# touch.net
KiCad netlist of a schematic drawn in EAGLE
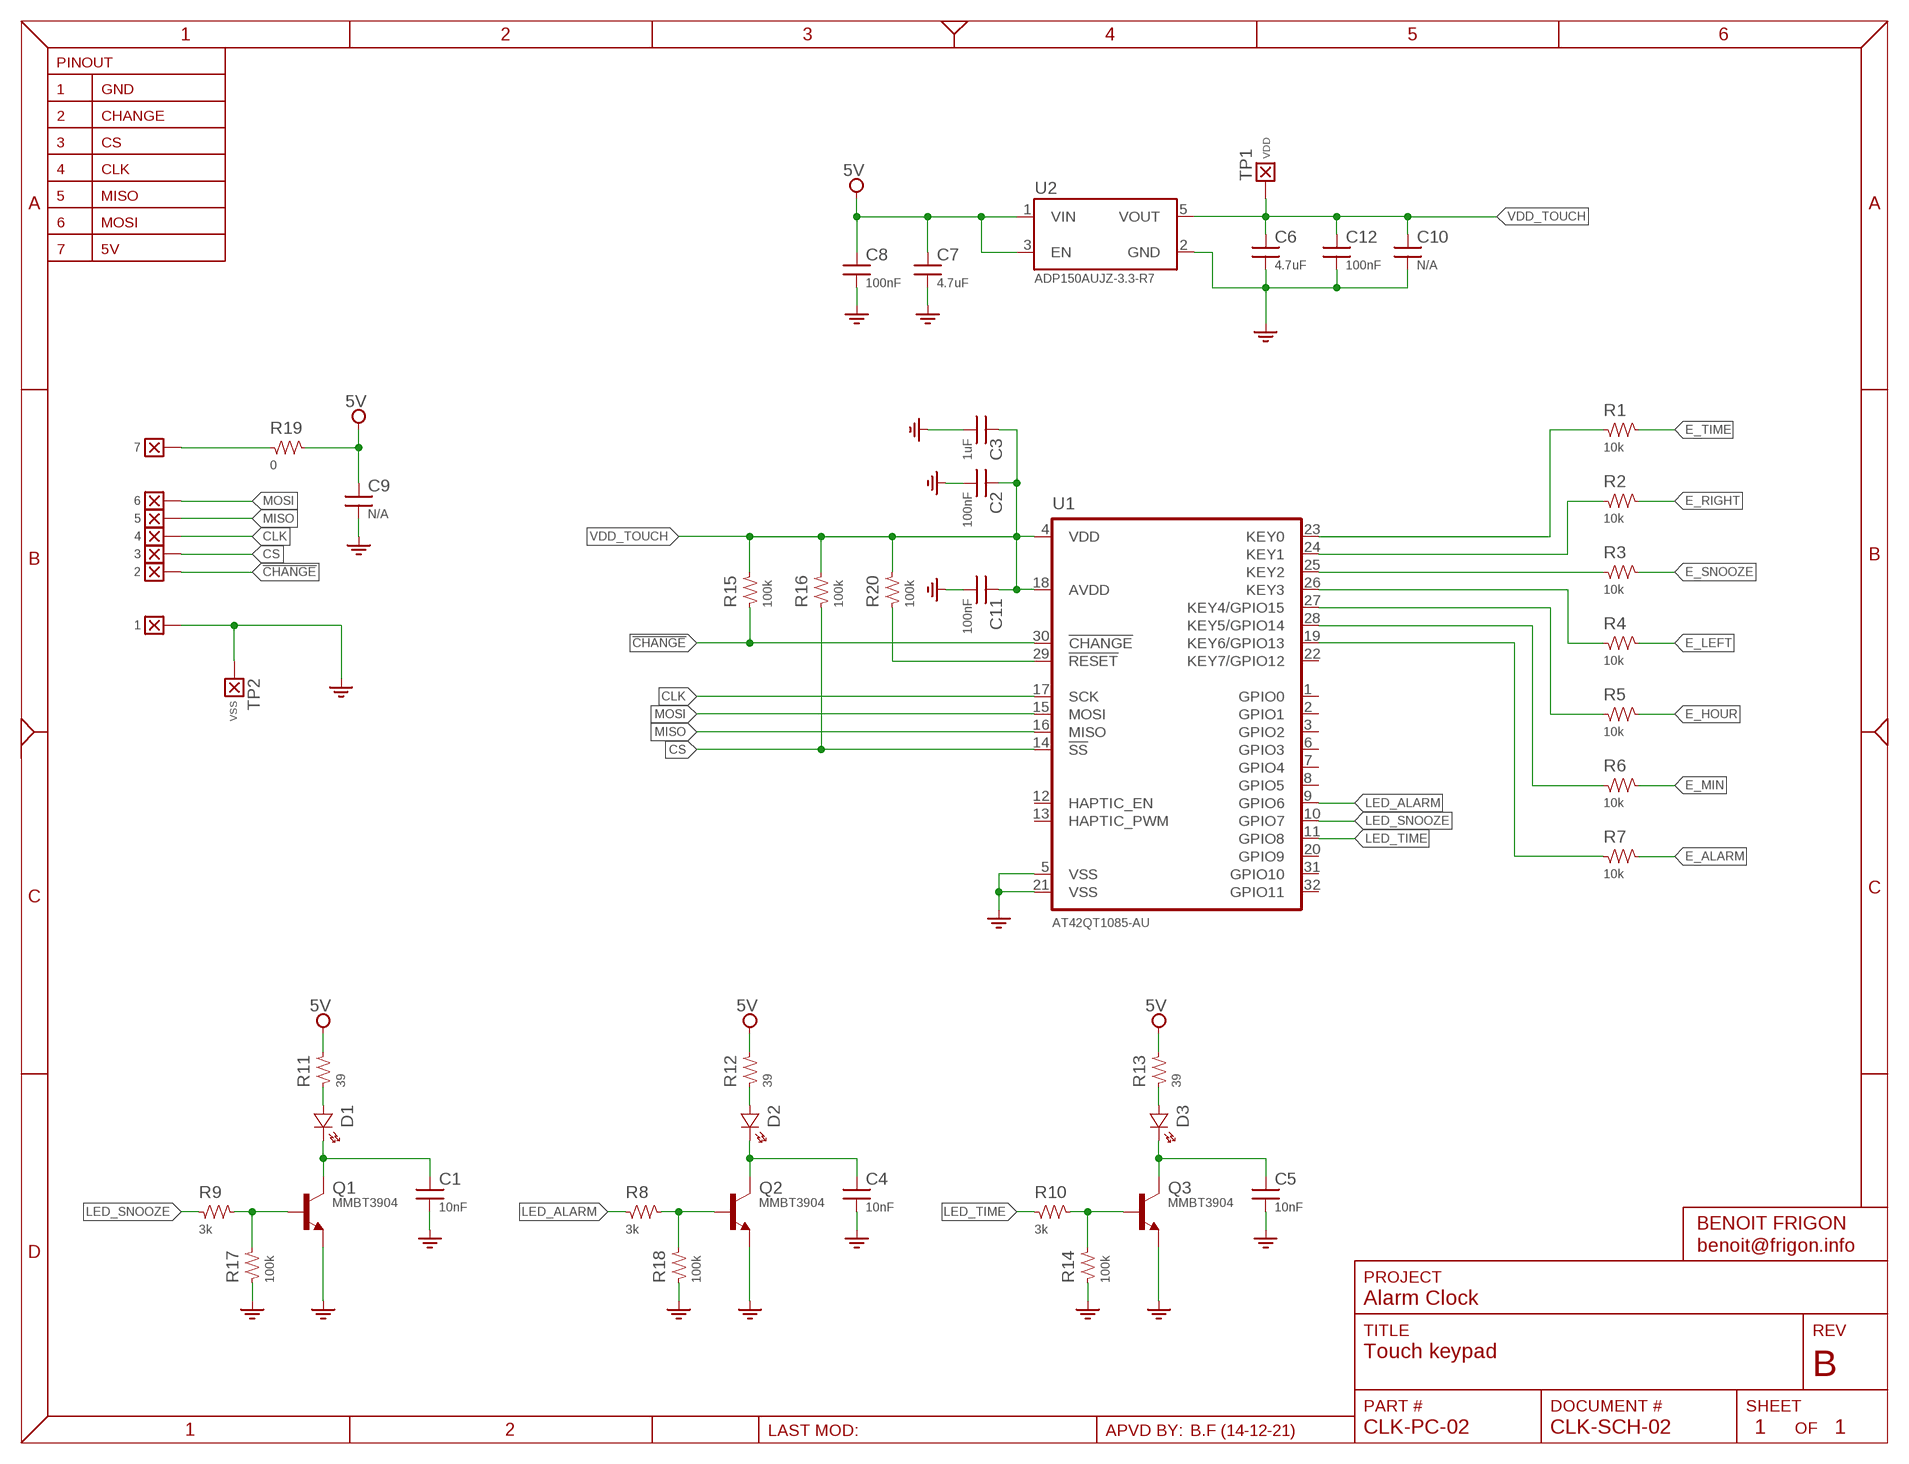
[diagram p0: schematic, sheet 1]

(export (version "E")
  (design (tool "Eeschema 10.0.6"))
  (components
    (comp (ref "!CHANGE")
      (value "2")
      (footprint "eagle-import:WIRE_SMT_125X50")
      (fields (field (name "BOM") "FALSE"))
      (libsource (lib "eagle-import") (part "WIRE-?125X50"))
    )
    (comp (ref "5V")
      (value "7")
      (footprint "eagle-import:WIRE_SMT_150X75")
      (libsource (lib "eagle-import") (part "WIRE-?150X75"))
    )
    (comp (ref "C1")
      (value "10nF")
      (footprint "eagle-import:SMD_0603")
      (libsource (lib "eagle-import") (part "CAP-0603"))
    )
    (comp (ref "C2")
      (value "100nF")
      (footprint "eagle-import:SMD_0603")
      (libsource (lib "eagle-import") (part "CAP-0603"))
    )
    (comp (ref "C3")
      (value "1uF")
      (footprint "eagle-import:SMD_1206")
      (description "{DESCRIPTION} - SMT 1206 - {value}")
      (fields (field (name "PACKAGE") "SMT 1206"))
      (libsource (lib "eagle-import") (part "CAP-1206"))
    )
    (comp (ref "C4")
      (value "10nF")
      (footprint "eagle-import:SMD_0603")
      (libsource (lib "eagle-import") (part "CAP-0603"))
    )
    (comp (ref "C5")
      (value "10nF")
      (footprint "eagle-import:SMD_0603")
      (libsource (lib "eagle-import") (part "CAP-0603"))
    )
    (comp (ref "C6")
      (value "4.7uF")
      (footprint "eagle-import:SMD_1206")
      (description "{DESCRIPTION} - SMT 1206 - {value}")
      (fields (field (name "PACKAGE") "SMT 1206"))
      (libsource (lib "eagle-import") (part "CAP-1206"))
    )
    (comp (ref "C7")
      (value "4.7uF")
      (footprint "eagle-import:SMD_1206")
      (description "{DESCRIPTION} - SMT 1206 - {value}")
      (fields (field (name "PACKAGE") "SMT 1206"))
      (libsource (lib "eagle-import") (part "CAP-1206"))
    )
    (comp (ref "C8")
      (value "100nF")
      (footprint "eagle-import:SMD_0603")
      (description "{DESCRIPTION} - SMT 0603 - {value}")
      (fields (field (name "PACKAGE") "SMT 0603"))
      (libsource (lib "eagle-import") (part "CAP-0603"))
    )
    (comp (ref "C9")
      (value "N/A")
      (footprint "eagle-import:SMD_1206")
      (libsource (lib "eagle-import") (part "CAP-1206"))
    )
    (comp (ref "C10")
      (value "N/A")
      (footprint "eagle-import:SMD_1206")
      (libsource (lib "eagle-import") (part "CAP-1206"))
    )
    (comp (ref "C11")
      (value "100nF")
      (footprint "eagle-import:SMD_0603")
      (description "{DESCRIPTION} - SMT 0603 - {value}")
      (fields (field (name "PACKAGE") "SMT 0603"))
      (libsource (lib "eagle-import") (part "CAP-0603"))
    )
    (comp (ref "C12")
      (value "100nF")
      (footprint "eagle-import:SMD_0603")
      (libsource (lib "eagle-import") (part "CAP-0603"))
    )
    (comp (ref "CLK")
      (value "4")
      (footprint "eagle-import:WIRE_SMT_125X50")
      (libsource (lib "eagle-import") (part "WIRE-?125X50"))
    )
    (comp (ref "CS")
      (value "3")
      (footprint "eagle-import:WIRE_SMT_125X50")
      (libsource (lib "eagle-import") (part "WIRE-?125X50"))
    )
    (comp (ref "D1")
      (value "{ATTR:COLOR}")
      (footprint "eagle-import:P47F")
      (description "{DESCRIPTION} - Red")
      (fields (field (name "MFG") "OSRAM") (field (name "COLOR") "Red"))
      (libsource (lib "eagle-import") (part "-P47FLR"))
    )
    (comp (ref "D2")
      (value "{ATTR:COLOR}")
      (footprint "eagle-import:P47F")
      (description "{DESCRIPTION} - Red")
      (fields (field (name "MFG") "OSRAM") (field (name "COLOR") "Red"))
      (libsource (lib "eagle-import") (part "-P47FLR"))
    )
    (comp (ref "D3")
      (value "{ATTR:COLOR}")
      (footprint "eagle-import:P47F")
      (description "{DESCRIPTION} - Red")
      (fields (field (name "MFG") "OSRAM") (field (name "COLOR") "Red"))
      (libsource (lib "eagle-import") (part "-P47FLR"))
    )
    (comp (ref "GND")
      (value "1")
      (footprint "eagle-import:WIRE_SMT_150X75")
      (libsource (lib "eagle-import") (part "WIRE-?150X75"))
    )
    (comp (ref "MISO")
      (value "5")
      (footprint "eagle-import:WIRE_SMT_125X50")
      (libsource (lib "eagle-import") (part "WIRE-?125X50"))
    )
    (comp (ref "MOSI")
      (value "6")
      (footprint "eagle-import:WIRE_SMT_125X50")
      (libsource (lib "eagle-import") (part "WIRE-?125X50"))
    )
    (comp (ref "Q1")
      (value "MMBT3904")
      (footprint "eagle-import:SOT23")
      (libsource (lib "eagle-import") (part "MMBT3904"))
    )
    (comp (ref "Q2")
      (value "MMBT3904")
      (footprint "eagle-import:SOT23")
      (libsource (lib "eagle-import") (part "MMBT3904"))
    )
    (comp (ref "Q3")
      (value "MMBT3904")
      (footprint "eagle-import:SOT23")
      (libsource (lib "eagle-import") (part "MMBT3904"))
    )
    (comp (ref "R1")
      (value "10k")
      (footprint "eagle-import:SMD_0603")
      (libsource (lib "eagle-import") (part "RES-0603"))
    )
    (comp (ref "R2")
      (value "10k")
      (footprint "eagle-import:SMD_0603")
      (description "{DESCRIPTION} - SMT 0603 - {VALUE}")
      (fields (field (name "PACKAGE") "SMT 0603"))
      (libsource (lib "eagle-import") (part "RES-0603"))
    )
    (comp (ref "R3")
      (value "10k")
      (footprint "eagle-import:SMD_0603")
      (description "{DESCRIPTION} - SMT 0603 - {VALUE}")
      (fields (field (name "PACKAGE") "SMT 0603"))
      (libsource (lib "eagle-import") (part "RES-0603"))
    )
    (comp (ref "R4")
      (value "10k")
      (footprint "eagle-import:SMD_0603")
      (description "{DESCRIPTION} - SMT 0603 - {VALUE}")
      (fields (field (name "PACKAGE") "SMT 0603"))
      (libsource (lib "eagle-import") (part "RES-0603"))
    )
    (comp (ref "R5")
      (value "10k")
      (footprint "eagle-import:SMD_0603")
      (description "{DESCRIPTION} - SMT 0603 - {VALUE}")
      (fields (field (name "PACKAGE") "SMT 0603"))
      (libsource (lib "eagle-import") (part "RES-0603"))
    )
    (comp (ref "R6")
      (value "10k")
      (footprint "eagle-import:SMD_0603")
      (description "{DESCRIPTION} - SMT 0603 - {VALUE}")
      (fields (field (name "PACKAGE") "SMT 0603"))
      (libsource (lib "eagle-import") (part "RES-0603"))
    )
    (comp (ref "R7")
      (value "10k")
      (footprint "eagle-import:SMD_0603")
      (description "{DESCRIPTION} - SMT 0603 - {VALUE}")
      (fields (field (name "PACKAGE") "SMT 0603"))
      (libsource (lib "eagle-import") (part "RES-0603"))
    )
    (comp (ref "R8")
      (value "3k")
      (footprint "eagle-import:SMD_0603")
      (libsource (lib "eagle-import") (part "RES-0603"))
    )
    (comp (ref "R9")
      (value "3k")
      (footprint "eagle-import:SMD_0603")
      (libsource (lib "eagle-import") (part "RES-0603"))
    )
    (comp (ref "R10")
      (value "3k")
      (footprint "eagle-import:SMD_0603")
      (libsource (lib "eagle-import") (part "RES-0603"))
    )
    (comp (ref "R11")
      (value "39")
      (footprint "eagle-import:SMD_0603")
      (libsource (lib "eagle-import") (part "RES-0603"))
    )
    (comp (ref "R12")
      (value "39")
      (footprint "eagle-import:SMD_0603")
      (libsource (lib "eagle-import") (part "RES-0603"))
    )
    (comp (ref "R13")
      (value "39")
      (footprint "eagle-import:SMD_0603")
      (libsource (lib "eagle-import") (part "RES-0603"))
    )
    (comp (ref "R14")
      (value "100k")
      (footprint "eagle-import:SMD_0603")
      (libsource (lib "eagle-import") (part "RES-0603"))
    )
    (comp (ref "R15")
      (value "100k")
      (footprint "eagle-import:SMD_0603")
      (libsource (lib "eagle-import") (part "RES-0603"))
    )
    (comp (ref "R16")
      (value "100k")
      (footprint "eagle-import:SMD_0603")
      (libsource (lib "eagle-import") (part "RES-0603"))
    )
    (comp (ref "R17")
      (value "100k")
      (footprint "eagle-import:SMD_0603")
      (libsource (lib "eagle-import") (part "RES-0603"))
    )
    (comp (ref "R18")
      (value "100k")
      (footprint "eagle-import:SMD_0603")
      (libsource (lib "eagle-import") (part "RES-0603"))
    )
    (comp (ref "R19")
      (value "0")
      (footprint "eagle-import:SMD_1206")
      (libsource (lib "eagle-import") (part "RES-1206"))
    )
    (comp (ref "R20")
      (value "100k")
      (footprint "eagle-import:SMD_0603")
      (description "{DESCRIPTION} - SMT 0603 - {VALUE}")
      (fields (field (name "PACKAGE") "SMT 0603"))
      (libsource (lib "eagle-import") (part "RES-0603"))
    )
    (comp (ref "TP1")
      (value "VDD")
      (footprint "eagle-import:TP_050")
      (libsource (lib "eagle-import") (part "TEST_POINT-050"))
    )
    (comp (ref "TP2")
      (value "VSS")
      (footprint "eagle-import:TP_050")
      (libsource (lib "eagle-import") (part "TEST_POINT-050"))
    )
    (comp (ref "U1")
      (value "AT42QT1085-AU")
      (footprint "eagle-import:TQFP-7X7-32")
      (libsource (lib "eagle-import") (part "AT42QT1085-?AU"))
    )
    (comp (ref "U2")
      (value "ADP150AUJZ-3.3-R7")
      (footprint "eagle-import:SOT23-5")
      (description "{DESCRIPTION} - 3.3v")
      (fields (field (name "MFG") "Analog Devices"))
      (libsource (lib "eagle-import") (part "ADP150A?Z--R7UJ3.3"))
    )
  )
  (nets
    (net (code "1") (name "/~{CHANGE}") (class "Default")
      (node (ref "!CHANGE") (pin "1") (pinfunction "P$1_1") (pintype "bidirectional"))
      (node (ref "R15") (pin "1") (pinfunction "1_1") (pintype "passive"))
      (node (ref "U1") (pin "30") (pinfunction "~{CHANGE}_30") (pintype "open_collector"))
    )
    (net (code "2") (name "5V") (class "Default")
      (node (ref "C7") (pin "1") (pinfunction "1_1") (pintype "passive"))
      (node (ref "C8") (pin "1") (pinfunction "1_1") (pintype "passive"))
      (node (ref "C9") (pin "1") (pinfunction "1_1") (pintype "passive"))
      (node (ref "R11") (pin "2") (pinfunction "2_2") (pintype "passive"))
      (node (ref "R12") (pin "2") (pinfunction "2_2") (pintype "passive"))
      (node (ref "R13") (pin "2") (pinfunction "2_2") (pintype "passive"))
      (node (ref "R19") (pin "2") (pinfunction "2_2") (pintype "passive"))
      (node (ref "U2") (pin "1") (pinfunction "VIN_1") (pintype "power_in"))
      (node (ref "U2") (pin "3") (pinfunction "EN_3") (pintype "input"))
    )
    (net (code "3") (name "CLK") (class "Default")
      (node (ref "CLK") (pin "1") (pinfunction "P$1_1") (pintype "bidirectional"))
      (node (ref "U1") (pin "17") (pinfunction "SCK_17") (pintype "input"))
    )
    (net (code "4") (name "CS") (class "Default")
      (node (ref "CS") (pin "1") (pinfunction "P$1_1") (pintype "bidirectional"))
      (node (ref "R16") (pin "1") (pinfunction "1_1") (pintype "passive"))
      (node (ref "U1") (pin "14") (pinfunction "~{SS}_14") (pintype "input"))
    )
    (net (code "5") (name "E_ALARM") (class "Default")
      (node (ref "R7") (pin "2") (pinfunction "2_2") (pintype "passive"))
    )
    (net (code "6") (name "E_HOUR") (class "Default")
      (node (ref "R5") (pin "2") (pinfunction "2_2") (pintype "passive"))
    )
    (net (code "7") (name "E_LEFT") (class "Default")
      (node (ref "R4") (pin "2") (pinfunction "2_2") (pintype "passive"))
    )
    (net (code "8") (name "E_MIN") (class "Default")
      (node (ref "R6") (pin "2") (pinfunction "2_2") (pintype "passive"))
    )
    (net (code "9") (name "E_RIGHT") (class "Default")
      (node (ref "R2") (pin "2") (pinfunction "2_2") (pintype "passive"))
    )
    (net (code "10") (name "E_SNOOZE") (class "Default")
      (node (ref "R3") (pin "2") (pinfunction "2_2") (pintype "passive"))
    )
    (net (code "11") (name "E_TIME") (class "Default")
      (node (ref "R1") (pin "2") (pinfunction "2_2") (pintype "passive"))
    )
    (net (code "12") (name "GND") (class "Default")
      (node (ref "C1") (pin "2") (pinfunction "2_2") (pintype "passive"))
      (node (ref "C10") (pin "2") (pinfunction "2_2") (pintype "passive"))
      (node (ref "C11") (pin "2") (pinfunction "2_2") (pintype "passive"))
      (node (ref "C12") (pin "2") (pinfunction "2_2") (pintype "passive"))
      (node (ref "C2") (pin "2") (pinfunction "2_2") (pintype "passive"))
      (node (ref "C3") (pin "2") (pinfunction "2_2") (pintype "passive"))
      (node (ref "C4") (pin "2") (pinfunction "2_2") (pintype "passive"))
      (node (ref "C5") (pin "2") (pinfunction "2_2") (pintype "passive"))
      (node (ref "C6") (pin "2") (pinfunction "2_2") (pintype "passive"))
      (node (ref "C7") (pin "2") (pinfunction "2_2") (pintype "passive"))
      (node (ref "C8") (pin "2") (pinfunction "2_2") (pintype "passive"))
      (node (ref "C9") (pin "2") (pinfunction "2_2") (pintype "passive"))
      (node (ref "GND") (pin "1") (pinfunction "P$1_1") (pintype "bidirectional"))
      (node (ref "Q1") (pin "2") (pinfunction "E_2") (pintype "passive"))
      (node (ref "Q2") (pin "2") (pinfunction "E_2") (pintype "passive"))
      (node (ref "Q3") (pin "2") (pinfunction "E_2") (pintype "passive"))
      (node (ref "R14") (pin "1") (pinfunction "1_1") (pintype "passive"))
      (node (ref "R17") (pin "1") (pinfunction "1_1") (pintype "passive"))
      (node (ref "R18") (pin "1") (pinfunction "1_1") (pintype "passive"))
      (node (ref "TP2") (pin "1") (pinfunction "P$1_1") (pintype "bidirectional"))
      (node (ref "U1") (pin "21") (pinfunction "VSS_21") (pintype "power_in"))
      (node (ref "U1") (pin "5") (pinfunction "VSS_5") (pintype "power_in"))
      (node (ref "U2") (pin "2") (pinfunction "GND_2") (pintype "power_in"))
    )
    (net (code "13") (name "LED_ALARM") (class "Default")
      (node (ref "R8") (pin "1") (pinfunction "1_1") (pintype "passive"))
      (node (ref "U1") (pin "9") (pinfunction "GPIO6_9") (pintype "bidirectional"))
    )
    (net (code "14") (name "LED_SNOOZE") (class "Default")
      (node (ref "R9") (pin "1") (pinfunction "1_1") (pintype "passive"))
      (node (ref "U1") (pin "10") (pinfunction "GPIO7_10") (pintype "bidirectional"))
    )
    (net (code "15") (name "LED_TIME") (class "Default")
      (node (ref "R10") (pin "1") (pinfunction "1_1") (pintype "passive"))
      (node (ref "U1") (pin "11") (pinfunction "GPIO8_11") (pintype "bidirectional"))
    )
    (net (code "16") (name "MISO") (class "Default")
      (node (ref "MISO") (pin "1") (pinfunction "P$1_1") (pintype "bidirectional"))
      (node (ref "U1") (pin "16") (pinfunction "MISO_16") (pintype "output"))
    )
    (net (code "17") (name "MOSI") (class "Default")
      (node (ref "MOSI") (pin "1") (pinfunction "P$1_1") (pintype "bidirectional"))
      (node (ref "U1") (pin "15") (pinfunction "MOSI_15") (pintype "input"))
    )
    (net (code "18") (name "Net-(5V-P$1)") (class "Default")
      (node (ref "5V") (pin "1") (pinfunction "P$1_1") (pintype "bidirectional"))
      (node (ref "R19") (pin "1") (pinfunction "1_1") (pintype "passive"))
    )
    (net (code "19") (name "Net-(D1-PadA)") (class "Default")
      (node (ref "D1") (pin "A") (pinfunction "A_A") (pintype "passive"))
      (node (ref "R11") (pin "1") (pinfunction "1_1") (pintype "passive"))
    )
    (net (code "20") (name "Net-(D2-PadA)") (class "Default")
      (node (ref "D2") (pin "A") (pinfunction "A_A") (pintype "passive"))
      (node (ref "R12") (pin "1") (pinfunction "1_1") (pintype "passive"))
    )
    (net (code "21") (name "Net-(D3-PadA)") (class "Default")
      (node (ref "D3") (pin "A") (pinfunction "A_A") (pintype "passive"))
      (node (ref "R13") (pin "1") (pinfunction "1_1") (pintype "passive"))
    )
    (net (code "22") (name "Net-(Q1-B)") (class "Default")
      (node (ref "Q1") (pin "1") (pinfunction "B_1") (pintype "passive"))
      (node (ref "R17") (pin "2") (pinfunction "2_2") (pintype "passive"))
      (node (ref "R9") (pin "2") (pinfunction "2_2") (pintype "passive"))
    )
    (net (code "23") (name "Net-(Q1-C)") (class "Default")
      (node (ref "C1") (pin "1") (pinfunction "1_1") (pintype "passive"))
      (node (ref "D1") (pin "K") (pinfunction "K_K") (pintype "passive"))
      (node (ref "Q1") (pin "3") (pinfunction "C_3") (pintype "passive"))
    )
    (net (code "24") (name "Net-(Q2-B)") (class "Default")
      (node (ref "Q2") (pin "1") (pinfunction "B_1") (pintype "passive"))
      (node (ref "R18") (pin "2") (pinfunction "2_2") (pintype "passive"))
      (node (ref "R8") (pin "2") (pinfunction "2_2") (pintype "passive"))
    )
    (net (code "25") (name "Net-(Q2-C)") (class "Default")
      (node (ref "C4") (pin "1") (pinfunction "1_1") (pintype "passive"))
      (node (ref "D2") (pin "K") (pinfunction "K_K") (pintype "passive"))
      (node (ref "Q2") (pin "3") (pinfunction "C_3") (pintype "passive"))
    )
    (net (code "26") (name "Net-(Q3-B)") (class "Default")
      (node (ref "Q3") (pin "1") (pinfunction "B_1") (pintype "passive"))
      (node (ref "R10") (pin "2") (pinfunction "2_2") (pintype "passive"))
      (node (ref "R14") (pin "2") (pinfunction "2_2") (pintype "passive"))
    )
    (net (code "27") (name "Net-(Q3-C)") (class "Default")
      (node (ref "C5") (pin "1") (pinfunction "1_1") (pintype "passive"))
      (node (ref "D3") (pin "K") (pinfunction "K_K") (pintype "passive"))
      (node (ref "Q3") (pin "3") (pinfunction "C_3") (pintype "passive"))
    )
    (net (code "28") (name "Net-(U1-KEY0)") (class "Default")
      (node (ref "R1") (pin "1") (pinfunction "1_1") (pintype "passive"))
      (node (ref "U1") (pin "23") (pinfunction "KEY0_23") (pintype "bidirectional"))
    )
    (net (code "29") (name "Net-(U1-KEY1)") (class "Default")
      (node (ref "R2") (pin "1") (pinfunction "1_1") (pintype "passive"))
      (node (ref "U1") (pin "24") (pinfunction "KEY1_24") (pintype "bidirectional"))
    )
    (net (code "30") (name "Net-(U1-KEY2)") (class "Default")
      (node (ref "R3") (pin "1") (pinfunction "1_1") (pintype "passive"))
      (node (ref "U1") (pin "25") (pinfunction "KEY2_25") (pintype "bidirectional"))
    )
    (net (code "31") (name "Net-(U1-KEY3)") (class "Default")
      (node (ref "R4") (pin "1") (pinfunction "1_1") (pintype "passive"))
      (node (ref "U1") (pin "26") (pinfunction "KEY3_26") (pintype "bidirectional"))
    )
    (net (code "32") (name "Net-(U1-KEY4{slash}GPIO15)") (class "Default")
      (node (ref "R5") (pin "1") (pinfunction "1_1") (pintype "passive"))
      (node (ref "U1") (pin "27") (pinfunction "KEY4/GPIO15_27") (pintype "bidirectional"))
    )
    (net (code "33") (name "Net-(U1-KEY5{slash}GPIO14)") (class "Default")
      (node (ref "R6") (pin "1") (pinfunction "1_1") (pintype "passive"))
      (node (ref "U1") (pin "28") (pinfunction "KEY5/GPIO14_28") (pintype "bidirectional"))
    )
    (net (code "34") (name "Net-(U1-KEY6{slash}GPIO13)") (class "Default")
      (node (ref "R7") (pin "1") (pinfunction "1_1") (pintype "passive"))
      (node (ref "U1") (pin "19") (pinfunction "KEY6/GPIO13_19") (pintype "bidirectional"))
    )
    (net (code "35") (name "Net-(U1-~{RESET})") (class "Default")
      (node (ref "R20") (pin "1") (pinfunction "1_1") (pintype "passive"))
      (node (ref "U1") (pin "29") (pinfunction "~{RESET}_29") (pintype "input"))
    )
    (net (code "36") (name "VDD_TOUCH") (class "Default")
      (node (ref "C10") (pin "1") (pinfunction "1_1") (pintype "passive"))
      (node (ref "C11") (pin "1") (pinfunction "1_1") (pintype "passive"))
      (node (ref "C12") (pin "1") (pinfunction "1_1") (pintype "passive"))
      (node (ref "C2") (pin "1") (pinfunction "1_1") (pintype "passive"))
      (node (ref "C3") (pin "1") (pinfunction "1_1") (pintype "passive"))
      (node (ref "C6") (pin "1") (pinfunction "1_1") (pintype "passive"))
      (node (ref "R15") (pin "2") (pinfunction "2_2") (pintype "passive"))
      (node (ref "R16") (pin "2") (pinfunction "2_2") (pintype "passive"))
      (node (ref "R20") (pin "2") (pinfunction "2_2") (pintype "passive"))
      (node (ref "TP1") (pin "1") (pinfunction "P$1_1") (pintype "bidirectional"))
      (node (ref "U1") (pin "18") (pinfunction "AVDD_18") (pintype "power_in"))
      (node (ref "U1") (pin "4") (pinfunction "VDD_4") (pintype "power_in"))
      (node (ref "U2") (pin "5") (pinfunction "VOUT_5") (pintype "power_in"))
    )
    (net (code "37") (name "unconnected-(U1-GPIO0-Pad1)") (class "Default")
      (node (ref "U1") (pin "1") (pinfunction "GPIO0_1") (pintype "bidirectional"))
    )
    (net (code "38") (name "unconnected-(U1-GPIO1-Pad2)") (class "Default")
      (node (ref "U1") (pin "2") (pinfunction "GPIO1_2") (pintype "bidirectional"))
    )
    (net (code "39") (name "unconnected-(U1-GPIO2-Pad3)") (class "Default")
      (node (ref "U1") (pin "3") (pinfunction "GPIO2_3") (pintype "bidirectional"))
    )
    (net (code "40") (name "unconnected-(U1-GPIO3-Pad6)") (class "Default")
      (node (ref "U1") (pin "6") (pinfunction "GPIO3_6") (pintype "bidirectional"))
    )
    (net (code "41") (name "unconnected-(U1-GPIO4-Pad7)") (class "Default")
      (node (ref "U1") (pin "7") (pinfunction "GPIO4_7") (pintype "bidirectional"))
    )
    (net (code "42") (name "unconnected-(U1-GPIO5-Pad8)") (class "Default")
      (node (ref "U1") (pin "8") (pinfunction "GPIO5_8") (pintype "bidirectional"))
    )
    (net (code "43") (name "unconnected-(U1-GPIO9-Pad20)") (class "Default")
      (node (ref "U1") (pin "20") (pinfunction "GPIO9_20") (pintype "bidirectional"))
    )
    (net (code "44") (name "unconnected-(U1-GPIO10-Pad31)") (class "Default")
      (node (ref "U1") (pin "31") (pinfunction "GPIO10_31") (pintype "bidirectional"))
    )
    (net (code "45") (name "unconnected-(U1-GPIO11-Pad32)") (class "Default")
      (node (ref "U1") (pin "32") (pinfunction "GPIO11_32") (pintype "bidirectional"))
    )
    (net (code "46") (name "unconnected-(U1-HAPTIC_EN-Pad12)") (class "Default")
      (node (ref "U1") (pin "12") (pinfunction "HAPTIC_EN_12") (pintype "output"))
    )
    (net (code "47") (name "unconnected-(U1-HAPTIC_PWM-Pad13)") (class "Default")
      (node (ref "U1") (pin "13") (pinfunction "HAPTIC_PWM_13") (pintype "output"))
    )
    (net (code "48") (name "unconnected-(U1-KEY7{slash}GPIO12-Pad22)") (class "Default")
      (node (ref "U1") (pin "22") (pinfunction "KEY7/GPIO12_22") (pintype "bidirectional"))
    )
  )
)
